# Sheet1.net
KiCad netlist of a schematic drawn in Altium Designer
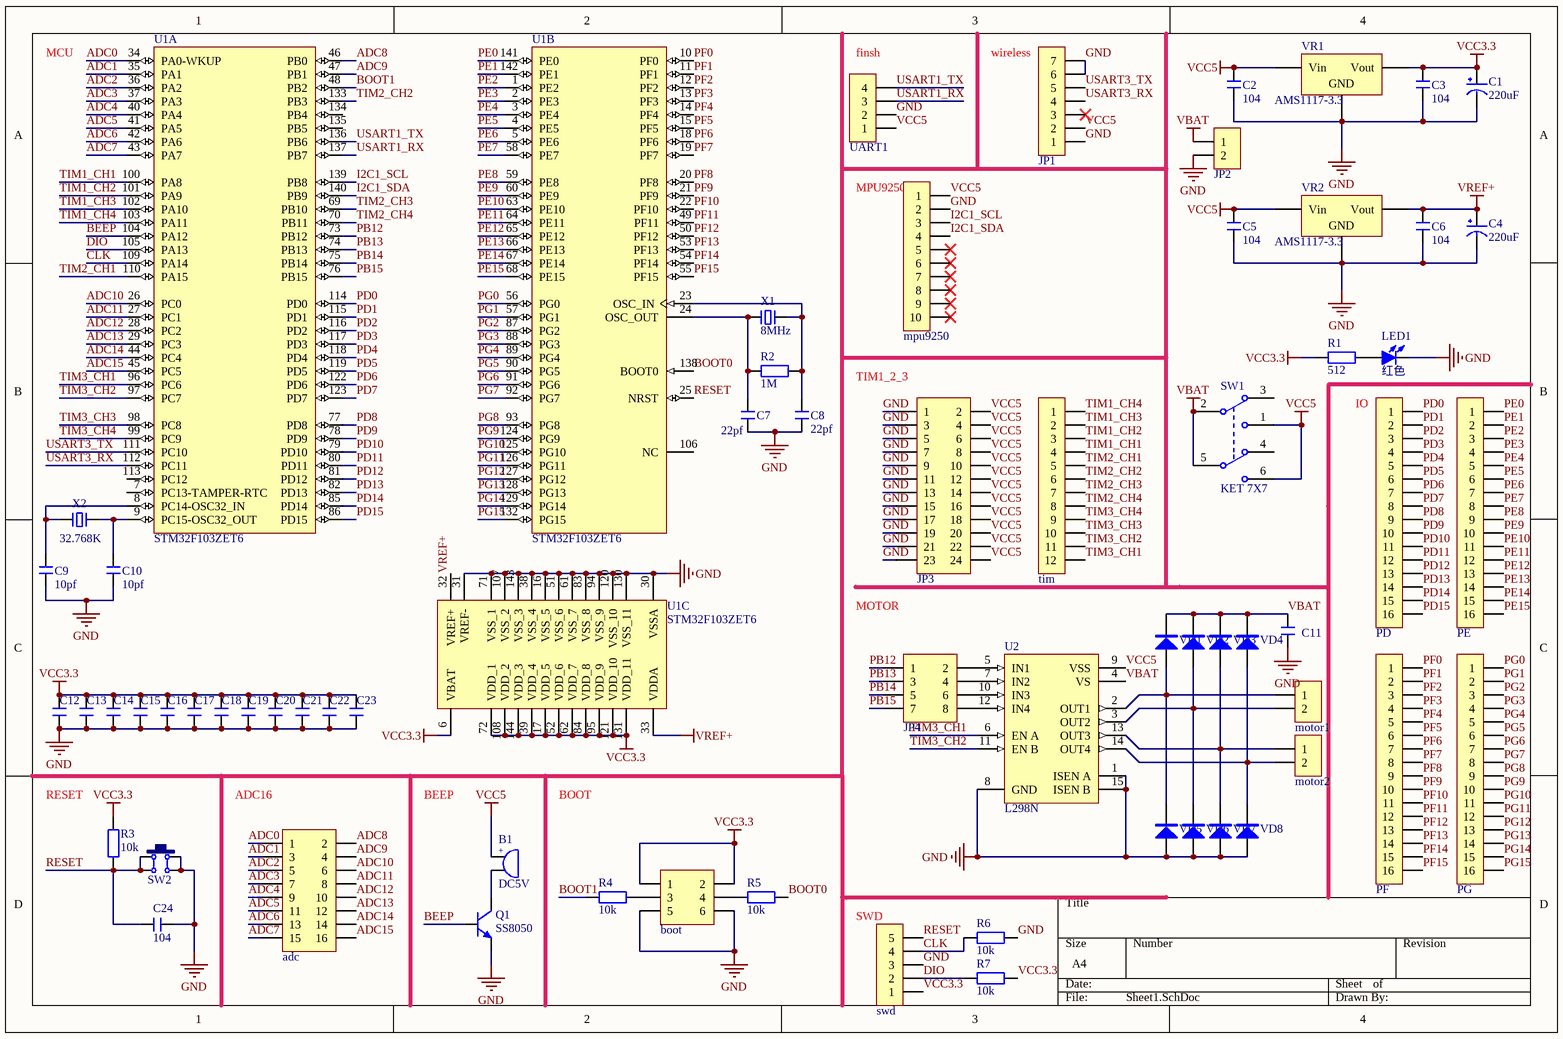
[diagram p0: Sheet1.SchDoc]

(export (version "E")
  (design (tool "Eeschema 10.0.6"))
  (components
    (comp (ref "adc")
      (value "Header 8X2")
      (footprint "HDR-8X2")
      (description "8*2P接插件")
      (fields (field (name "版权归属") "源创客"))
      (libsource (lib "接插件") (part "Header 8X2"))
    )
    (comp (ref "B1")
      (value "DC5V")
      (footprint "BEEP 5x9x5.5")
      (description "蜂鸣器")
      (fields (field (name "版权归属") "源创客"))
      (libsource (lib "未分类器件") (part "BEEP"))
    )
    (comp (ref "boot")
      (value "Header3X2")
      (footprint "HDR2X3")
      (description "3*2P接插件")
      (fields (field (name "版权归属") "源创客"))
      (libsource (lib "接插件") (part "Header 3X2"))
    )
    (comp (ref "C1")
      (value "220uF")
      (footprint "CC6.56.5")
      (libsource (lib "WarShip V3 STM32103封装库") (part "CAP"))
    )
    (comp (ref "C2")
      (value "104")
      (footprint "0805")
      (description "无极性贴片电容")
      (fields (field (name "版权归属") "源创客"))
      (libsource (lib "电阻-电容-电感") (part "C"))
    )
    (comp (ref "C3")
      (value "104")
      (footprint "0805")
      (description "无极性贴片电容")
      (fields (field (name "版权归属") "源创客"))
      (libsource (lib "电阻-电容-电感") (part "C"))
    )
    (comp (ref "C4")
      (value "220uF")
      (footprint "CC6.56.5")
      (libsource (lib "WarShip V3 STM32103封装库") (part "CAP"))
    )
    (comp (ref "C5")
      (value "104")
      (footprint "0805")
      (description "无极性贴片电容")
      (fields (field (name "版权归属") "源创客"))
      (libsource (lib "电阻-电容-电感") (part "C"))
    )
    (comp (ref "C6")
      (value "104")
      (footprint "0805")
      (description "无极性贴片电容")
      (fields (field (name "版权归属") "源创客"))
      (libsource (lib "电阻-电容-电感") (part "C"))
    )
    (comp (ref "C7")
      (value "22pf")
      (footprint "0805")
      (description "无极性贴片电容")
      (fields (field (name "版权归属") "源创客"))
      (libsource (lib "电阻-电容-电感") (part "C"))
    )
    (comp (ref "C8")
      (value "22pf")
      (footprint "0805")
      (description "无极性贴片电容")
      (fields (field (name "版权归属") "源创客"))
      (libsource (lib "电阻-电容-电感") (part "C"))
    )
    (comp (ref "C9")
      (value "10pf")
      (footprint "0805")
      (description "无极性贴片电容")
      (fields (field (name "版权归属") "源创客"))
      (libsource (lib "电阻-电容-电感") (part "C"))
    )
    (comp (ref "C10")
      (value "10pf")
      (footprint "0805")
      (description "无极性贴片电容")
      (fields (field (name "版权归属") "源创客"))
      (libsource (lib "电阻-电容-电感") (part "C"))
    )
    (comp (ref "C11")
      (value "104")
      (footprint "C 0805")
      (description "无极性贴片电容")
      (fields (field (name "版权归属") "源创客"))
      (libsource (lib "电阻-电容-电感") (part "C"))
    )
    (comp (ref "C12")
      (value "104")
      (footprint "C 0805")
      (description "无极性贴片电容")
      (fields (field (name "版权归属") "源创客"))
      (libsource (lib "电阻-电容-电感") (part "C"))
    )
    (comp (ref "C13")
      (value "104")
      (footprint "C 0805")
      (description "无极性贴片电容")
      (fields (field (name "版权归属") "源创客"))
      (libsource (lib "电阻-电容-电感") (part "C"))
    )
    (comp (ref "C14")
      (value "104")
      (footprint "C 0805")
      (description "无极性贴片电容")
      (fields (field (name "版权归属") "源创客"))
      (libsource (lib "电阻-电容-电感") (part "C"))
    )
    (comp (ref "C15")
      (value "104")
      (footprint "C 0805")
      (description "无极性贴片电容")
      (fields (field (name "版权归属") "源创客"))
      (libsource (lib "电阻-电容-电感") (part "C"))
    )
    (comp (ref "C16")
      (value "104")
      (footprint "C 0805")
      (description "无极性贴片电容")
      (fields (field (name "版权归属") "源创客"))
      (libsource (lib "电阻-电容-电感") (part "C"))
    )
    (comp (ref "C17")
      (value "104")
      (footprint "C 0805")
      (description "无极性贴片电容")
      (fields (field (name "版权归属") "源创客"))
      (libsource (lib "电阻-电容-电感") (part "C"))
    )
    (comp (ref "C18")
      (value "104")
      (footprint "C 0805")
      (description "无极性贴片电容")
      (fields (field (name "版权归属") "源创客"))
      (libsource (lib "电阻-电容-电感") (part "C"))
    )
    (comp (ref "C19")
      (value "104")
      (footprint "C 0805")
      (description "无极性贴片电容")
      (fields (field (name "版权归属") "源创客"))
      (libsource (lib "电阻-电容-电感") (part "C"))
    )
    (comp (ref "C20")
      (value "104")
      (footprint "C 0805")
      (description "无极性贴片电容")
      (fields (field (name "版权归属") "源创客"))
      (libsource (lib "电阻-电容-电感") (part "C"))
    )
    (comp (ref "C21")
      (value "104")
      (footprint "C 0805")
      (description "无极性贴片电容")
      (fields (field (name "版权归属") "源创客"))
      (libsource (lib "电阻-电容-电感") (part "C"))
    )
    (comp (ref "C22")
      (value "104")
      (footprint "C 0805")
      (description "无极性贴片电容")
      (fields (field (name "版权归属") "源创客"))
      (libsource (lib "电阻-电容-电感") (part "C"))
    )
    (comp (ref "C23")
      (value "104")
      (footprint "C 0805")
      (description "无极性贴片电容")
      (fields (field (name "版权归属") "源创客"))
      (libsource (lib "电阻-电容-电感") (part "C"))
    )
    (comp (ref "C24")
      (value "104")
      (footprint "0805")
      (description "无极性贴片电容")
      (fields (field (name "版权归属") "源创客"))
      (libsource (lib "电阻-电容-电感") (part "C"))
    )
    (comp (ref "JP1")
      (value "HDR-1X7")
      (footprint "HDR-1X7_M")
      (description "7P接插件")
      (fields (field (name "版权归属") "源创客"))
      (libsource (lib "接插件") (part "Header 7"))
    )
    (comp (ref "JP2")
      (value "HDR-1X2")
      (footprint "KF350-2P")
      (description "2P接插件")
      (fields (field (name "版权归属") "源创客"))
      (libsource (lib "接插件") (part "Header 2"))
    )
    (comp (ref "JP3")
      (value "Header 2X11")
      (footprint "HDR-12X2")
      (description "12*2P接插件")
      (fields (field (name "版权归属") "源创客"))
      (libsource (lib "接插件") (part "Header 12X2"))
    )
    (comp (ref "JP4")
      (value "Header 4X2")
      (footprint "HDR-4X2")
      (description "4*2P接插件")
      (fields (field (name "版权归属") "源创客"))
      (libsource (lib "接插件") (part "Header 4X2"))
    )
    (comp (ref "LED1")
      (value "红色")
      (footprint "LED 3MM-R")
      (description "插件LED")
      (fields (field (name "版权归属") "源创客"))
      (libsource (lib "LED") (part "LED-3MM"))
    )
    (comp (ref "motor1")
      (value "HDR-1X2")
      (footprint "KF128-3.81-2P")
      (description "2P接插件")
      (fields (field (name "版权归属") "源创客"))
      (libsource (lib "接插件") (part "Header 2"))
    )
    (comp (ref "motor2")
      (value "HDR-1X2")
      (footprint "KF128-3.81-2P")
      (description "2P接插件")
      (fields (field (name "版权归属") "源创客"))
      (libsource (lib "接插件") (part "Header 2"))
    )
    (comp (ref "mpu9250")
      (value "HDR-1X10")
      (footprint "HDR-1X10_M")
      (description "10P接插件")
      (fields (field (name "版权归属") "源创客"))
      (libsource (lib "接插件") (part "Header 10"))
    )
    (comp (ref "PD")
      (value "HDR-1X16")
      (footprint "HDR-1X16")
      (description "16P接插件")
      (fields (field (name "版权归属") "源创客"))
      (libsource (lib "接插件") (part "Header 16"))
    )
    (comp (ref "PE")
      (value "HDR-1X16")
      (footprint "HDR-1X16")
      (description "16P接插件")
      (fields (field (name "版权归属") "源创客"))
      (libsource (lib "接插件") (part "Header 16"))
    )
    (comp (ref "PF")
      (value "HDR-1X16")
      (footprint "HDR-1X16")
      (description "16P接插件")
      (fields (field (name "版权归属") "源创客"))
      (libsource (lib "接插件") (part "Header 16"))
    )
    (comp (ref "PG")
      (value "HDR-1X16")
      (footprint "HDR-1X16")
      (description "16P接插件")
      (fields (field (name "版权归属") "源创客"))
      (libsource (lib "接插件") (part "Header 16"))
    )
    (comp (ref "Q1")
      (value "SS8050")
      (footprint "TO92A")
      (description "高频放大-NPN型")
      (fields (field (name "版权归属") "源创客"))
      (libsource (lib "三极管") (part "8050-DIP"))
    )
    (comp (ref "R1")
      (value "512")
      (footprint "0805")
      (description "贴片电阻")
      (fields (field (name "版权归属") "源创客"))
      (libsource (lib "电阻-电容-电感") (part "R"))
    )
    (comp (ref "R2")
      (value "1M")
      (footprint "0805")
      (description "贴片电阻")
      (fields (field (name "版权归属") "源创客"))
      (libsource (lib "电阻-电容-电感") (part "R"))
    )
    (comp (ref "R3")
      (value "10k")
      (footprint "0805")
      (description "贴片电阻")
      (fields (field (name "版权归属") "源创客"))
      (libsource (lib "电阻-电容-电感") (part "R"))
    )
    (comp (ref "R4")
      (value "10k")
      (footprint "0805")
      (description "贴片电阻")
      (fields (field (name "版权归属") "源创客"))
      (libsource (lib "电阻-电容-电感") (part "R"))
    )
    (comp (ref "R5")
      (value "10k")
      (footprint "0805")
      (description "贴片电阻")
      (fields (field (name "版权归属") "源创客"))
      (libsource (lib "电阻-电容-电感") (part "R"))
    )
    (comp (ref "R6")
      (value "10k")
      (footprint "R 0805")
      (description "贴片电阻")
      (fields (field (name "版权归属") "源创客"))
      (libsource (lib "电阻-电容-电感") (part "R"))
    )
    (comp (ref "R7")
      (value "10k")
      (footprint "R 0805")
      (description "贴片电阻")
      (fields (field (name "版权归属") "源创客"))
      (libsource (lib "电阻-电容-电感") (part "R"))
    )
    (comp (ref "SW1")
      (value "KET 7X7")
      (footprint "KFT DIP-7X7")
      (description "7*7自锁开关")
      (fields (field (name "版权归属") "源创客"))
      (libsource (lib "按键-开关") (part "KET 7X7"))
    )
    (comp (ref "SW2")
      (value "6x6x5")
      (footprint "TSW DIP-6*6*5")
      (description "直插6x6轻触开关")
      (fields (field (name "版权归属") "源创客"))
      (libsource (lib "按键-开关") (part "TSW DIP-6x6"))
    )
    (comp (ref "swd")
      (value "HDR-1X5")
      (footprint "HDR-1X5")
      (description "5P接插件")
      (fields (field (name "版权归属") "源创客"))
      (libsource (lib "接插件") (part "Header 5"))
    )
    (comp (ref "tim")
      (value "HDR-1X12")
      (footprint "HDR-1X12_M")
      (description "12P接插件")
      (fields (field (name "版权归属") "源创客"))
      (libsource (lib "接插件") (part "Header 12"))
    )
    (comp (ref "U1")
      (value "STM32F103ZET6")
      (footprint "STM-LQFP144_M")
      (libsource (lib "") (part "STM32F103ZET6_1"))
    )
    (comp (ref "U2")
      (value "L298N")
      (footprint "Multiwatt15V")
      (description "Dual Full Bridge Driver")
      (fields (field (name "PUBLISHER") "Altium Limited"))
      (libsource (lib "ST Interface DC Motor Controller") (part "L298N"))
    )
    (comp (ref "UART1")
      (value "HDR-1X4")
      (footprint "HDR1X4")
      (description "4P接插件")
      (fields (field (name "版权归属") "源创客"))
      (libsource (lib "接插件") (part "Header 4"))
    )
    (comp (ref "VD1")
      (value "1N4007")
      (footprint "SMA")
      (description "整流二极管")
      (fields (field (name "版权归属") "源创客"))
      (libsource (lib "二极管-整流桥") (part "1N4007"))
    )
    (comp (ref "VD2")
      (value "1N4007")
      (footprint "SMA")
      (description "整流二极管")
      (fields (field (name "版权归属") "源创客"))
      (libsource (lib "二极管-整流桥") (part "1N4007"))
    )
    (comp (ref "VD3")
      (value "1N4007")
      (footprint "SMA")
      (description "整流二极管")
      (fields (field (name "版权归属") "源创客"))
      (libsource (lib "二极管-整流桥") (part "1N4007"))
    )
    (comp (ref "VD4")
      (value "1N4007")
      (footprint "SMA")
      (description "整流二极管")
      (fields (field (name "版权归属") "源创客"))
      (libsource (lib "二极管-整流桥") (part "1N4007"))
    )
    (comp (ref "VD5")
      (value "1N4007")
      (footprint "SMA")
      (description "整流二极管")
      (fields (field (name "版权归属") "源创客"))
      (libsource (lib "二极管-整流桥") (part "1N4007"))
    )
    (comp (ref "VD6")
      (value "1N4007")
      (footprint "SMA")
      (description "整流二极管")
      (fields (field (name "版权归属") "源创客"))
      (libsource (lib "二极管-整流桥") (part "1N4007"))
    )
    (comp (ref "VD7")
      (value "1N4007")
      (footprint "SMA")
      (description "整流二极管")
      (fields (field (name "版权归属") "源创客"))
      (libsource (lib "二极管-整流桥") (part "1N4007"))
    )
    (comp (ref "VD8")
      (value "1N4007")
      (footprint "SMA")
      (description "整流二极管")
      (fields (field (name "版权归属") "源创客"))
      (libsource (lib "二极管-整流桥") (part "1N4007"))
    )
    (comp (ref "VR1")
      (value "AMS1117-3.3")
      (footprint "SOT-223")
      (description "低压差线性稳压(LDO)")
      (libsource (lib "Miscellaneous Devices LC") (part "SOT-223 AMS1117-3.3"))
    )
    (comp (ref "VR2")
      (value "AMS1117-3.3")
      (footprint "SOT-223")
      (description "低压差线性稳压(LDO)")
      (libsource (lib "Miscellaneous Devices LC") (part "SOT-223 AMS1117-3.3"))
    )
    (comp (ref "X1")
      (value "8MHz")
      (footprint "XTAL-49S DIP")
      (description "2脚晶振")
      (fields (field (name "版权归属") "源创客"))
      (libsource (lib "保险丝-晶振") (part "XTAL-2"))
    )
    (comp (ref "X2")
      (value "32.768K")
      (footprint "CAPR5-4X5")
      (description "2脚晶振")
      (fields (field (name "版权归属") "源创客"))
      (libsource (lib "保险丝-晶振") (part "XTAL-2"))
    )
  )
  (nets
    (net (code "1") (name "/ADC0") (class "Default")
      (node (ref "U1") (pin "34") (pinfunction "PA0-WKUP_34") (pintype "bidirectional"))
      (node (ref "adc") (pin "1") (pinfunction "1_1") (pintype "passive"))
    )
    (net (code "2") (name "/ADC1") (class "Default")
      (node (ref "U1") (pin "35") (pinfunction "PA1_35") (pintype "bidirectional"))
      (node (ref "adc") (pin "3") (pinfunction "3_3") (pintype "passive"))
    )
    (net (code "3") (name "/ADC2") (class "Default")
      (node (ref "U1") (pin "36") (pinfunction "PA2_36") (pintype "bidirectional"))
      (node (ref "adc") (pin "5") (pinfunction "5_5") (pintype "passive"))
    )
    (net (code "4") (name "/ADC3") (class "Default")
      (node (ref "U1") (pin "37") (pinfunction "PA3_37") (pintype "bidirectional"))
      (node (ref "adc") (pin "7") (pinfunction "7_7") (pintype "passive"))
    )
    (net (code "5") (name "/ADC4") (class "Default")
      (node (ref "U1") (pin "40") (pinfunction "PA4_40") (pintype "bidirectional"))
      (node (ref "adc") (pin "9") (pinfunction "9_9") (pintype "passive"))
    )
    (net (code "6") (name "/ADC5") (class "Default")
      (node (ref "U1") (pin "41") (pinfunction "PA5_41") (pintype "bidirectional"))
      (node (ref "adc") (pin "11") (pinfunction "11_11") (pintype "passive"))
    )
    (net (code "7") (name "/ADC6") (class "Default")
      (node (ref "U1") (pin "42") (pinfunction "PA6_42") (pintype "bidirectional"))
      (node (ref "adc") (pin "13") (pinfunction "13_13") (pintype "passive"))
    )
    (net (code "8") (name "/ADC7") (class "Default")
      (node (ref "U1") (pin "43") (pinfunction "PA7_43") (pintype "bidirectional"))
      (node (ref "adc") (pin "15") (pinfunction "15_15") (pintype "passive"))
    )
    (net (code "9") (name "/ADC8") (class "Default")
      (node (ref "U1") (pin "46") (pinfunction "PB0_46") (pintype "bidirectional"))
      (node (ref "adc") (pin "2") (pinfunction "2_2") (pintype "passive"))
    )
    (net (code "10") (name "/ADC9") (class "Default")
      (node (ref "U1") (pin "47") (pinfunction "PB1_47") (pintype "bidirectional"))
      (node (ref "adc") (pin "4") (pinfunction "4_4") (pintype "passive"))
    )
    (net (code "11") (name "/ADC10") (class "Default")
      (node (ref "U1") (pin "26") (pinfunction "PC0_26") (pintype "bidirectional"))
      (node (ref "adc") (pin "6") (pinfunction "6_6") (pintype "passive"))
    )
    (net (code "12") (name "/ADC11") (class "Default")
      (node (ref "U1") (pin "27") (pinfunction "PC1_27") (pintype "bidirectional"))
      (node (ref "adc") (pin "8") (pinfunction "8_8") (pintype "passive"))
    )
    (net (code "13") (name "/ADC12") (class "Default")
      (node (ref "U1") (pin "28") (pinfunction "PC2_28") (pintype "bidirectional"))
      (node (ref "adc") (pin "10") (pinfunction "10_10") (pintype "passive"))
    )
    (net (code "14") (name "/ADC13") (class "Default")
      (node (ref "U1") (pin "29") (pinfunction "PC3_29") (pintype "bidirectional"))
      (node (ref "adc") (pin "12") (pinfunction "12_12") (pintype "passive"))
    )
    (net (code "15") (name "/ADC14") (class "Default")
      (node (ref "U1") (pin "44") (pinfunction "PC4_44") (pintype "bidirectional"))
      (node (ref "adc") (pin "14") (pinfunction "14_14") (pintype "passive"))
    )
    (net (code "16") (name "/ADC15") (class "Default")
      (node (ref "U1") (pin "45") (pinfunction "PC5_45") (pintype "bidirectional"))
      (node (ref "adc") (pin "16") (pinfunction "16_16") (pintype "passive"))
    )
    (net (code "17") (name "/BEEP") (class "Default")
      (node (ref "Q1") (pin "2") (pinfunction "B_2") (pintype "passive"))
      (node (ref "U1") (pin "104") (pinfunction "PA12_104") (pintype "bidirectional"))
    )
    (net (code "18") (name "/BOOT0") (class "Default")
      (node (ref "R5") (pin "1") (pinfunction "1_1") (pintype "passive"))
      (node (ref "U1") (pin "138") (pinfunction "BOOT0_138") (pintype "input"))
    )
    (net (code "19") (name "/BOOT1") (class "Default")
      (node (ref "R4") (pin "1") (pinfunction "1_1") (pintype "passive"))
      (node (ref "U1") (pin "48") (pinfunction "PB2_48") (pintype "bidirectional"))
    )
    (net (code "20") (name "/CLK") (class "Default")
      (node (ref "R6") (pin "1") (pinfunction "1_1") (pintype "passive"))
      (node (ref "U1") (pin "109") (pinfunction "PA14_109") (pintype "bidirectional"))
      (node (ref "swd") (pin "4") (pinfunction "4_4") (pintype "passive"))
    )
    (net (code "21") (name "/DIO") (class "Default")
      (node (ref "R7") (pin "1") (pinfunction "1_1") (pintype "passive"))
      (node (ref "U1") (pin "105") (pinfunction "PA13_105") (pintype "bidirectional"))
      (node (ref "swd") (pin "2") (pinfunction "2_2") (pintype "passive"))
    )
    (net (code "22") (name "/I2C1_SCL") (class "Default")
      (node (ref "U1") (pin "139") (pinfunction "PB8_139") (pintype "bidirectional"))
      (node (ref "mpu9250") (pin "3") (pinfunction "3_3") (pintype "passive"))
    )
    (net (code "23") (name "/I2C1_SDA") (class "Default")
      (node (ref "U1") (pin "140") (pinfunction "PB9_140") (pintype "bidirectional"))
      (node (ref "mpu9250") (pin "4") (pinfunction "4_4") (pintype "passive"))
    )
    (net (code "24") (name "/PB12") (class "Default")
      (node (ref "JP4") (pin "1") (pinfunction "1_1") (pintype "passive"))
      (node (ref "U1") (pin "73") (pinfunction "PB12_73") (pintype "bidirectional"))
    )
    (net (code "25") (name "/PB13") (class "Default")
      (node (ref "JP4") (pin "3") (pinfunction "3_3") (pintype "passive"))
      (node (ref "U1") (pin "74") (pinfunction "PB13_74") (pintype "bidirectional"))
    )
    (net (code "26") (name "/PB14") (class "Default")
      (node (ref "JP4") (pin "5") (pinfunction "5_5") (pintype "passive"))
      (node (ref "U1") (pin "75") (pinfunction "PB14_75") (pintype "bidirectional"))
    )
    (net (code "27") (name "/PB15") (class "Default")
      (node (ref "JP4") (pin "7") (pinfunction "7_7") (pintype "passive"))
      (node (ref "U1") (pin "76") (pinfunction "PB15_76") (pintype "bidirectional"))
    )
    (net (code "28") (name "/PD0") (class "Default")
      (node (ref "PD") (pin "1") (pinfunction "1_1") (pintype "passive"))
      (node (ref "U1") (pin "114") (pinfunction "PD0_114") (pintype "bidirectional"))
    )
    (net (code "29") (name "/PD1") (class "Default")
      (node (ref "PD") (pin "2") (pinfunction "2_2") (pintype "passive"))
      (node (ref "U1") (pin "115") (pinfunction "PD1_115") (pintype "bidirectional"))
    )
    (net (code "30") (name "/PD2") (class "Default")
      (node (ref "PD") (pin "3") (pinfunction "3_3") (pintype "passive"))
      (node (ref "U1") (pin "116") (pinfunction "PD2_116") (pintype "bidirectional"))
    )
    (net (code "31") (name "/PD3") (class "Default")
      (node (ref "PD") (pin "4") (pinfunction "4_4") (pintype "passive"))
      (node (ref "U1") (pin "117") (pinfunction "PD3_117") (pintype "bidirectional"))
    )
    (net (code "32") (name "/PD4") (class "Default")
      (node (ref "PD") (pin "5") (pinfunction "5_5") (pintype "passive"))
      (node (ref "U1") (pin "118") (pinfunction "PD4_118") (pintype "bidirectional"))
    )
    (net (code "33") (name "/PD5") (class "Default")
      (node (ref "PD") (pin "6") (pinfunction "6_6") (pintype "passive"))
      (node (ref "U1") (pin "119") (pinfunction "PD5_119") (pintype "bidirectional"))
    )
    (net (code "34") (name "/PD6") (class "Default")
      (node (ref "PD") (pin "7") (pinfunction "7_7") (pintype "passive"))
      (node (ref "U1") (pin "122") (pinfunction "PD6_122") (pintype "bidirectional"))
    )
    (net (code "35") (name "/PD7") (class "Default")
      (node (ref "PD") (pin "8") (pinfunction "8_8") (pintype "passive"))
      (node (ref "U1") (pin "123") (pinfunction "PD7_123") (pintype "bidirectional"))
    )
    (net (code "36") (name "/PD8") (class "Default")
      (node (ref "PD") (pin "9") (pinfunction "9_9") (pintype "passive"))
      (node (ref "U1") (pin "77") (pinfunction "PD8_77") (pintype "bidirectional"))
    )
    (net (code "37") (name "/PD9") (class "Default")
      (node (ref "PD") (pin "10") (pinfunction "10_10") (pintype "passive"))
      (node (ref "U1") (pin "78") (pinfunction "PD9_78") (pintype "bidirectional"))
    )
    (net (code "38") (name "/PD10") (class "Default")
      (node (ref "PD") (pin "11") (pinfunction "11_11") (pintype "passive"))
      (node (ref "U1") (pin "79") (pinfunction "PD10_79") (pintype "bidirectional"))
    )
    (net (code "39") (name "/PD11") (class "Default")
      (node (ref "PD") (pin "12") (pinfunction "12_12") (pintype "passive"))
      (node (ref "U1") (pin "80") (pinfunction "PD11_80") (pintype "bidirectional"))
    )
    (net (code "40") (name "/PD12") (class "Default")
      (node (ref "PD") (pin "13") (pinfunction "13_13") (pintype "passive"))
      (node (ref "U1") (pin "81") (pinfunction "PD12_81") (pintype "bidirectional"))
    )
    (net (code "41") (name "/PD13") (class "Default")
      (node (ref "PD") (pin "14") (pinfunction "14_14") (pintype "passive"))
      (node (ref "U1") (pin "82") (pinfunction "PD13_82") (pintype "bidirectional"))
    )
    (net (code "42") (name "/PD14") (class "Default")
      (node (ref "PD") (pin "15") (pinfunction "15_15") (pintype "passive"))
      (node (ref "U1") (pin "85") (pinfunction "PD14_85") (pintype "bidirectional"))
    )
    (net (code "43") (name "/PD15") (class "Default")
      (node (ref "PD") (pin "16") (pinfunction "16_16") (pintype "passive"))
      (node (ref "U1") (pin "86") (pinfunction "PD15_86") (pintype "bidirectional"))
    )
    (net (code "44") (name "/PE0") (class "Default")
      (node (ref "PE") (pin "1") (pinfunction "1_1") (pintype "passive"))
      (node (ref "U1") (pin "141") (pinfunction "PE0_141") (pintype "bidirectional"))
    )
    (net (code "45") (name "/PE1") (class "Default")
      (node (ref "PE") (pin "2") (pinfunction "2_2") (pintype "passive"))
      (node (ref "U1") (pin "142") (pinfunction "PE1_142") (pintype "bidirectional"))
    )
    (net (code "46") (name "/PE2") (class "Default")
      (node (ref "PE") (pin "3") (pinfunction "3_3") (pintype "passive"))
      (node (ref "U1") (pin "1") (pinfunction "PE2_1") (pintype "bidirectional"))
    )
    (net (code "47") (name "/PE3") (class "Default")
      (node (ref "PE") (pin "4") (pinfunction "4_4") (pintype "passive"))
      (node (ref "U1") (pin "2") (pinfunction "PE3_2") (pintype "bidirectional"))
    )
    (net (code "48") (name "/PE4") (class "Default")
      (node (ref "PE") (pin "5") (pinfunction "5_5") (pintype "passive"))
      (node (ref "U1") (pin "3") (pinfunction "PE4_3") (pintype "bidirectional"))
    )
    (net (code "49") (name "/PE5") (class "Default")
      (node (ref "PE") (pin "6") (pinfunction "6_6") (pintype "passive"))
      (node (ref "U1") (pin "4") (pinfunction "PE5_4") (pintype "bidirectional"))
    )
    (net (code "50") (name "/PE6") (class "Default")
      (node (ref "PE") (pin "7") (pinfunction "7_7") (pintype "passive"))
      (node (ref "U1") (pin "5") (pinfunction "PE6_5") (pintype "bidirectional"))
    )
    (net (code "51") (name "/PE7") (class "Default")
      (node (ref "PE") (pin "8") (pinfunction "8_8") (pintype "passive"))
      (node (ref "U1") (pin "58") (pinfunction "PE7_58") (pintype "bidirectional"))
    )
    (net (code "52") (name "/PE8") (class "Default")
      (node (ref "PE") (pin "9") (pinfunction "9_9") (pintype "passive"))
      (node (ref "U1") (pin "59") (pinfunction "PE8_59") (pintype "bidirectional"))
    )
    (net (code "53") (name "/PE9") (class "Default")
      (node (ref "PE") (pin "10") (pinfunction "10_10") (pintype "passive"))
      (node (ref "U1") (pin "60") (pinfunction "PE9_60") (pintype "bidirectional"))
    )
    (net (code "54") (name "/PE10") (class "Default")
      (node (ref "PE") (pin "11") (pinfunction "11_11") (pintype "passive"))
      (node (ref "U1") (pin "63") (pinfunction "PE10_63") (pintype "bidirectional"))
    )
    (net (code "55") (name "/PE11") (class "Default")
      (node (ref "PE") (pin "12") (pinfunction "12_12") (pintype "passive"))
      (node (ref "U1") (pin "64") (pinfunction "PE11_64") (pintype "bidirectional"))
    )
    (net (code "56") (name "/PE12") (class "Default")
      (node (ref "PE") (pin "13") (pinfunction "13_13") (pintype "passive"))
      (node (ref "U1") (pin "65") (pinfunction "PE12_65") (pintype "bidirectional"))
    )
    (net (code "57") (name "/PE13") (class "Default")
      (node (ref "PE") (pin "14") (pinfunction "14_14") (pintype "passive"))
      (node (ref "U1") (pin "66") (pinfunction "PE13_66") (pintype "bidirectional"))
    )
    (net (code "58") (name "/PE14") (class "Default")
      (node (ref "PE") (pin "15") (pinfunction "15_15") (pintype "passive"))
      (node (ref "U1") (pin "67") (pinfunction "PE14_67") (pintype "bidirectional"))
    )
    (net (code "59") (name "/PE15") (class "Default")
      (node (ref "PE") (pin "16") (pinfunction "16_16") (pintype "passive"))
      (node (ref "U1") (pin "68") (pinfunction "PE15_68") (pintype "bidirectional"))
    )
    (net (code "60") (name "/PF0") (class "Default")
      (node (ref "PF") (pin "1") (pinfunction "1_1") (pintype "passive"))
      (node (ref "U1") (pin "10") (pinfunction "PF0_10") (pintype "bidirectional"))
    )
    (net (code "61") (name "/PF1") (class "Default")
      (node (ref "PF") (pin "2") (pinfunction "2_2") (pintype "passive"))
      (node (ref "U1") (pin "11") (pinfunction "PF1_11") (pintype "bidirectional"))
    )
    (net (code "62") (name "/PF2") (class "Default")
      (node (ref "PF") (pin "3") (pinfunction "3_3") (pintype "passive"))
      (node (ref "U1") (pin "12") (pinfunction "PF2_12") (pintype "bidirectional"))
    )
    (net (code "63") (name "/PF3") (class "Default")
      (node (ref "PF") (pin "4") (pinfunction "4_4") (pintype "passive"))
      (node (ref "U1") (pin "13") (pinfunction "PF3_13") (pintype "bidirectional"))
    )
    (net (code "64") (name "/PF4") (class "Default")
      (node (ref "PF") (pin "5") (pinfunction "5_5") (pintype "passive"))
      (node (ref "U1") (pin "14") (pinfunction "PF4_14") (pintype "bidirectional"))
    )
    (net (code "65") (name "/PF5") (class "Default")
      (node (ref "PF") (pin "6") (pinfunction "6_6") (pintype "passive"))
      (node (ref "U1") (pin "15") (pinfunction "PF5_15") (pintype "bidirectional"))
    )
    (net (code "66") (name "/PF6") (class "Default")
      (node (ref "PF") (pin "7") (pinfunction "7_7") (pintype "passive"))
      (node (ref "U1") (pin "18") (pinfunction "PF6_18") (pintype "bidirectional"))
    )
    (net (code "67") (name "/PF7") (class "Default")
      (node (ref "PF") (pin "8") (pinfunction "8_8") (pintype "passive"))
      (node (ref "U1") (pin "19") (pinfunction "PF7_19") (pintype "bidirectional"))
    )
    (net (code "68") (name "/PF8") (class "Default")
      (node (ref "PF") (pin "9") (pinfunction "9_9") (pintype "passive"))
      (node (ref "U1") (pin "20") (pinfunction "PF8_20") (pintype "bidirectional"))
    )
    (net (code "69") (name "/PF9") (class "Default")
      (node (ref "PF") (pin "10") (pinfunction "10_10") (pintype "passive"))
      (node (ref "U1") (pin "21") (pinfunction "PF9_21") (pintype "bidirectional"))
    )
    (net (code "70") (name "/PF10") (class "Default")
      (node (ref "PF") (pin "11") (pinfunction "11_11") (pintype "passive"))
      (node (ref "U1") (pin "22") (pinfunction "PF10_22") (pintype "bidirectional"))
    )
    (net (code "71") (name "/PF11") (class "Default")
      (node (ref "PF") (pin "12") (pinfunction "12_12") (pintype "passive"))
      (node (ref "U1") (pin "49") (pinfunction "PF11_49") (pintype "bidirectional"))
    )
    (net (code "72") (name "/PF12") (class "Default")
      (node (ref "PF") (pin "13") (pinfunction "13_13") (pintype "passive"))
      (node (ref "U1") (pin "50") (pinfunction "PF12_50") (pintype "bidirectional"))
    )
    (net (code "73") (name "/PF13") (class "Default")
      (node (ref "PF") (pin "14") (pinfunction "14_14") (pintype "passive"))
      (node (ref "U1") (pin "53") (pinfunction "PF13_53") (pintype "bidirectional"))
    )
    (net (code "74") (name "/PF14") (class "Default")
      (node (ref "PF") (pin "15") (pinfunction "15_15") (pintype "passive"))
      (node (ref "U1") (pin "54") (pinfunction "PF14_54") (pintype "bidirectional"))
    )
    (net (code "75") (name "/PF15") (class "Default")
      (node (ref "PF") (pin "16") (pinfunction "16_16") (pintype "passive"))
      (node (ref "U1") (pin "55") (pinfunction "PF15_55") (pintype "bidirectional"))
    )
    (net (code "76") (name "/PG0") (class "Default")
      (node (ref "PG") (pin "1") (pinfunction "1_1") (pintype "passive"))
      (node (ref "U1") (pin "56") (pinfunction "PG0_56") (pintype "bidirectional"))
    )
    (net (code "77") (name "/PG1") (class "Default")
      (node (ref "PG") (pin "2") (pinfunction "2_2") (pintype "passive"))
      (node (ref "U1") (pin "57") (pinfunction "PG1_57") (pintype "bidirectional"))
    )
    (net (code "78") (name "/PG2") (class "Default")
      (node (ref "PG") (pin "3") (pinfunction "3_3") (pintype "passive"))
      (node (ref "U1") (pin "87") (pinfunction "PG2_87") (pintype "bidirectional"))
    )
    (net (code "79") (name "/PG3") (class "Default")
      (node (ref "PG") (pin "4") (pinfunction "4_4") (pintype "passive"))
      (node (ref "U1") (pin "88") (pinfunction "PG3_88") (pintype "bidirectional"))
    )
    (net (code "80") (name "/PG4") (class "Default")
      (node (ref "PG") (pin "5") (pinfunction "5_5") (pintype "passive"))
      (node (ref "U1") (pin "89") (pinfunction "PG4_89") (pintype "bidirectional"))
    )
    (net (code "81") (name "/PG5") (class "Default")
      (node (ref "PG") (pin "6") (pinfunction "6_6") (pintype "passive"))
      (node (ref "U1") (pin "90") (pinfunction "PG5_90") (pintype "bidirectional"))
    )
    (net (code "82") (name "/PG6") (class "Default")
      (node (ref "PG") (pin "7") (pinfunction "7_7") (pintype "passive"))
      (node (ref "U1") (pin "91") (pinfunction "PG6_91") (pintype "bidirectional"))
    )
    (net (code "83") (name "/PG7") (class "Default")
      (node (ref "PG") (pin "8") (pinfunction "8_8") (pintype "passive"))
      (node (ref "U1") (pin "92") (pinfunction "PG7_92") (pintype "bidirectional"))
    )
    (net (code "84") (name "/PG8") (class "Default")
      (node (ref "PG") (pin "9") (pinfunction "9_9") (pintype "passive"))
      (node (ref "U1") (pin "93") (pinfunction "PG8_93") (pintype "bidirectional"))
    )
    (net (code "85") (name "/PG9") (class "Default")
      (node (ref "PG") (pin "10") (pinfunction "10_10") (pintype "passive"))
      (node (ref "U1") (pin "124") (pinfunction "PG9_124") (pintype "bidirectional"))
    )
    (net (code "86") (name "/PG10") (class "Default")
      (node (ref "PG") (pin "11") (pinfunction "11_11") (pintype "passive"))
      (node (ref "U1") (pin "125") (pinfunction "PG10_125") (pintype "bidirectional"))
    )
    (net (code "87") (name "/PG11") (class "Default")
      (node (ref "PG") (pin "12") (pinfunction "12_12") (pintype "passive"))
      (node (ref "U1") (pin "126") (pinfunction "PG11_126") (pintype "bidirectional"))
    )
    (net (code "88") (name "/PG12") (class "Default")
      (node (ref "PG") (pin "13") (pinfunction "13_13") (pintype "passive"))
      (node (ref "U1") (pin "127") (pinfunction "PG12_127") (pintype "bidirectional"))
    )
    (net (code "89") (name "/PG13") (class "Default")
      (node (ref "PG") (pin "14") (pinfunction "14_14") (pintype "passive"))
      (node (ref "U1") (pin "128") (pinfunction "PG13_128") (pintype "bidirectional"))
    )
    (net (code "90") (name "/PG14") (class "Default")
      (node (ref "PG") (pin "15") (pinfunction "15_15") (pintype "passive"))
      (node (ref "U1") (pin "129") (pinfunction "PG14_129") (pintype "bidirectional"))
    )
    (net (code "91") (name "/PG15") (class "Default")
      (node (ref "PG") (pin "16") (pinfunction "16_16") (pintype "passive"))
      (node (ref "U1") (pin "132") (pinfunction "PG15_132") (pintype "bidirectional"))
    )
    (net (code "92") (name "/RESET") (class "Default")
      (node (ref "C24") (pin "1") (pinfunction "1_1") (pintype "passive"))
      (node (ref "R3") (pin "1") (pinfunction "1_1") (pintype "passive"))
      (node (ref "SW2") (pin "1") (pinfunction "1_1") (pintype "passive"))
      (node (ref "SW2") (pin "4") (pinfunction "4_4") (pintype "passive"))
      (node (ref "U1") (pin "25") (pinfunction "NRST_25") (pintype "bidirectional"))
      (node (ref "swd") (pin "5") (pinfunction "5_5") (pintype "passive"))
    )
    (net (code "93") (name "/TIM1_CH1") (class "Default")
      (node (ref "U1") (pin "100") (pinfunction "PA8_100") (pintype "bidirectional"))
      (node (ref "tim") (pin "4") (pinfunction "4_4") (pintype "passive"))
    )
    (net (code "94") (name "/TIM1_CH2") (class "Default")
      (node (ref "U1") (pin "101") (pinfunction "PA9_101") (pintype "bidirectional"))
      (node (ref "tim") (pin "3") (pinfunction "3_3") (pintype "passive"))
    )
    (net (code "95") (name "/TIM1_CH3") (class "Default")
      (node (ref "U1") (pin "102") (pinfunction "PA10_102") (pintype "bidirectional"))
      (node (ref "tim") (pin "2") (pinfunction "2_2") (pintype "passive"))
    )
    (net (code "96") (name "/TIM1_CH4") (class "Default")
      (node (ref "U1") (pin "103") (pinfunction "PA11_103") (pintype "bidirectional"))
      (node (ref "tim") (pin "1") (pinfunction "1_1") (pintype "passive"))
    )
    (net (code "97") (name "/TIM2_CH1") (class "Default")
      (node (ref "U1") (pin "110") (pinfunction "PA15_110") (pintype "bidirectional"))
      (node (ref "tim") (pin "5") (pinfunction "5_5") (pintype "passive"))
    )
    (net (code "98") (name "/TIM2_CH2") (class "Default")
      (node (ref "U1") (pin "133") (pinfunction "PB3_133") (pintype "bidirectional"))
      (node (ref "tim") (pin "6") (pinfunction "6_6") (pintype "passive"))
    )
    (net (code "99") (name "/TIM2_CH3") (class "Default")
      (node (ref "U1") (pin "69") (pinfunction "PB10_69") (pintype "bidirectional"))
      (node (ref "tim") (pin "7") (pinfunction "7_7") (pintype "passive"))
    )
    (net (code "100") (name "/TIM2_CH4") (class "Default")
      (node (ref "U1") (pin "70") (pinfunction "PB11_70") (pintype "bidirectional"))
      (node (ref "tim") (pin "8") (pinfunction "8_8") (pintype "passive"))
    )
    (net (code "101") (name "/TIM3_CH1") (class "Default")
      (node (ref "U1") (pin "96") (pinfunction "PC6_96") (pintype "bidirectional"))
      (node (ref "U2") (pin "6") (pinfunction "EN_A_6") (pintype "input"))
      (node (ref "tim") (pin "12") (pinfunction "12_12") (pintype "passive"))
    )
    (net (code "102") (name "/TIM3_CH2") (class "Default")
      (node (ref "U1") (pin "97") (pinfunction "PC7_97") (pintype "bidirectional"))
      (node (ref "U2") (pin "11") (pinfunction "EN_B_11") (pintype "input"))
      (node (ref "tim") (pin "11") (pinfunction "11_11") (pintype "passive"))
    )
    (net (code "103") (name "/TIM3_CH3") (class "Default")
      (node (ref "U1") (pin "98") (pinfunction "PC8_98") (pintype "bidirectional"))
      (node (ref "tim") (pin "10") (pinfunction "10_10") (pintype "passive"))
    )
    (net (code "104") (name "/TIM3_CH4") (class "Default")
      (node (ref "U1") (pin "99") (pinfunction "PC9_99") (pintype "bidirectional"))
      (node (ref "tim") (pin "9") (pinfunction "9_9") (pintype "passive"))
    )
    (net (code "105") (name "/USART1_RX") (class "Default")
      (node (ref "U1") (pin "137") (pinfunction "PB7_137") (pintype "bidirectional"))
      (node (ref "UART1") (pin "3") (pinfunction "3_3") (pintype "passive"))
    )
    (net (code "106") (name "/USART1_TX") (class "Default")
      (node (ref "U1") (pin "136") (pinfunction "PB6_136") (pintype "bidirectional"))
      (node (ref "UART1") (pin "4") (pinfunction "4_4") (pintype "passive"))
    )
    (net (code "107") (name "/USART3_RX") (class "Default")
      (node (ref "JP1") (pin "4") (pinfunction "4_4") (pintype "passive"))
      (node (ref "U1") (pin "112") (pinfunction "PC11_112") (pintype "bidirectional"))
    )
    (net (code "108") (name "/USART3_TX") (class "Default")
      (node (ref "JP1") (pin "5") (pinfunction "5_5") (pintype "passive"))
      (node (ref "U1") (pin "111") (pinfunction "PC10_111") (pintype "bidirectional"))
    )
    (net (code "109") (name "GND") (class "Default")
      (node (ref "C1") (pin "2") (pinfunction "GND_2") (pintype "passive"))
      (node (ref "C10") (pin "1") (pinfunction "1_1") (pintype "passive"))
      (node (ref "C11") (pin "2") (pinfunction "2_2") (pintype "passive"))
      (node (ref "C12") (pin "2") (pinfunction "2_2") (pintype "passive"))
      (node (ref "C13") (pin "2") (pinfunction "2_2") (pintype "passive"))
      (node (ref "C14") (pin "2") (pinfunction "2_2") (pintype "passive"))
      (node (ref "C15") (pin "2") (pinfunction "2_2") (pintype "passive"))
      (node (ref "C16") (pin "2") (pinfunction "2_2") (pintype "passive"))
      (node (ref "C17") (pin "2") (pinfunction "2_2") (pintype "passive"))
      (node (ref "C18") (pin "2") (pinfunction "2_2") (pintype "passive"))
      (node (ref "C19") (pin "2") (pinfunction "2_2") (pintype "passive"))
      (node (ref "C2") (pin "2") (pinfunction "2_2") (pintype "passive"))
      (node (ref "C20") (pin "2") (pinfunction "2_2") (pintype "passive"))
      (node (ref "C21") (pin "2") (pinfunction "2_2") (pintype "passive"))
      (node (ref "C22") (pin "2") (pinfunction "2_2") (pintype "passive"))
      (node (ref "C23") (pin "2") (pinfunction "2_2") (pintype "passive"))
      (node (ref "C24") (pin "2") (pinfunction "2_2") (pintype "passive"))
      (node (ref "C3") (pin "2") (pinfunction "2_2") (pintype "passive"))
      (node (ref "C4") (pin "2") (pinfunction "GND_2") (pintype "passive"))
      (node (ref "C5") (pin "2") (pinfunction "2_2") (pintype "passive"))
      (node (ref "C6") (pin "2") (pinfunction "2_2") (pintype "passive"))
      (node (ref "C7") (pin "2") (pinfunction "2_2") (pintype "passive"))
      (node (ref "C8") (pin "2") (pinfunction "2_2") (pintype "passive"))
      (node (ref "C9") (pin "1") (pinfunction "1_1") (pintype "passive"))
      (node (ref "JP1") (pin "1") (pinfunction "1_1") (pintype "passive"))
      (node (ref "JP1") (pin "6") (pinfunction "6_6") (pintype "passive"))
      (node (ref "JP1") (pin "7") (pinfunction "7_7") (pintype "passive"))
      (node (ref "JP2") (pin "2") (pinfunction "2_2") (pintype "passive"))
      (node (ref "JP3") (pin "1") (pinfunction "1_1") (pintype "passive"))
      (node (ref "JP3") (pin "11") (pinfunction "11_11") (pintype "passive"))
      (node (ref "JP3") (pin "13") (pinfunction "13_13") (pintype "passive"))
      (node (ref "JP3") (pin "15") (pinfunction "15_15") (pintype "passive"))
      (node (ref "JP3") (pin "17") (pinfunction "17_17") (pintype "passive"))
      (node (ref "JP3") (pin "19") (pinfunction "19_19") (pintype "passive"))
      (node (ref "JP3") (pin "21") (pinfunction "21_21") (pintype "passive"))
      (node (ref "JP3") (pin "23") (pinfunction "23_23") (pintype "passive"))
      (node (ref "JP3") (pin "3") (pinfunction "3_3") (pintype "passive"))
      (node (ref "JP3") (pin "5") (pinfunction "5_5") (pintype "passive"))
      (node (ref "JP3") (pin "7") (pinfunction "7_7") (pintype "passive"))
      (node (ref "JP3") (pin "9") (pinfunction "9_9") (pintype "passive"))
      (node (ref "LED1") (pin "2") (pinfunction "K_2") (pintype "passive"))
      (node (ref "Q1") (pin "1") (pinfunction "E_1") (pintype "passive"))
      (node (ref "R6") (pin "2") (pinfunction "2_2") (pintype "passive"))
      (node (ref "SW2") (pin "2") (pinfunction "2_2") (pintype "passive"))
      (node (ref "SW2") (pin "3") (pinfunction "3_3") (pintype "passive"))
      (node (ref "U1") (pin "107") (pinfunction "VSS_2_107") (pintype "power_in"))
      (node (ref "U1") (pin "120") (pinfunction "VSS_10_120") (pintype "power_in"))
      (node (ref "U1") (pin "130") (pinfunction "VSS_11_130") (pintype "power_in"))
      (node (ref "U1") (pin "143") (pinfunction "VSS_3_143") (pintype "power_in"))
      (node (ref "U1") (pin "16") (pinfunction "VSS_5_16") (pintype "power_in"))
      (node (ref "U1") (pin "30") (pinfunction "VSSA_30") (pintype "power_in"))
      (node (ref "U1") (pin "31") (pinfunction "VREF-_31") (pintype "power_in"))
      (node (ref "U1") (pin "38") (pinfunction "VSS_4_38") (pintype "power_in"))
      (node (ref "U1") (pin "51") (pinfunction "VSS_6_51") (pintype "power_in"))
      (node (ref "U1") (pin "61") (pinfunction "VSS_7_61") (pintype "power_in"))
      (node (ref "U1") (pin "71") (pinfunction "VSS_1_71") (pintype "power_in"))
      (node (ref "U1") (pin "83") (pinfunction "VSS_8_83") (pintype "power_in"))
      (node (ref "U1") (pin "94") (pinfunction "VSS_9_94") (pintype "power_in"))
      (node (ref "U2") (pin "1") (pinfunction "ISEN_A_1") (pintype "passive"))
      (node (ref "U2") (pin "15") (pinfunction "ISEN_B_15") (pintype "passive"))
      (node (ref "U2") (pin "8") (pinfunction "GND_8") (pintype "power_in"))
      (node (ref "UART1") (pin "2") (pinfunction "2_2") (pintype "passive"))
      (node (ref "VD5") (pin "1") (pinfunction "A_1") (pintype "passive"))
      (node (ref "VD6") (pin "1") (pinfunction "A_1") (pintype "passive"))
      (node (ref "VD7") (pin "1") (pinfunction "A_1") (pintype "passive"))
      (node (ref "VD8") (pin "1") (pinfunction "A_1") (pintype "passive"))
      (node (ref "VR1") (pin "1") (pinfunction "GND_1") (pintype "passive"))
      (node (ref "VR2") (pin "1") (pinfunction "GND_1") (pintype "passive"))
      (node (ref "boot") (pin "5") (pinfunction "5_5") (pintype "passive"))
      (node (ref "boot") (pin "6") (pinfunction "6_6") (pintype "passive"))
      (node (ref "mpu9250") (pin "2") (pinfunction "2_2") (pintype "passive"))
      (node (ref "swd") (pin "3") (pinfunction "3_3") (pintype "passive"))
    )
    (net (code "110") (name "Net-(LED1-A)") (class "Default")
      (node (ref "LED1") (pin "1") (pinfunction "A_1") (pintype "passive"))
      (node (ref "R1") (pin "2") (pinfunction "2_2") (pintype "passive"))
    )
    (net (code "111") (name "Net-(Q1-C)") (class "Default")
      (node (ref "B1") (pin "2") (pinfunction "2_2") (pintype "passive"))
      (node (ref "Q1") (pin "3") (pinfunction "C_3") (pintype "passive"))
    )
    (net (code "112") (name "Net-(R4-Pad2)") (class "Default")
      (node (ref "R4") (pin "2") (pinfunction "2_2") (pintype "passive"))
      (node (ref "boot") (pin "3") (pinfunction "3_3") (pintype "passive"))
    )
    (net (code "113") (name "Net-(R5-Pad2)") (class "Default")
      (node (ref "R5") (pin "2") (pinfunction "2_2") (pintype "passive"))
      (node (ref "boot") (pin "4") (pinfunction "4_4") (pintype "passive"))
    )
    (net (code "114") (name "Net-(U1A-PC14-OSC32_IN)") (class "Default")
      (node (ref "C9") (pin "2") (pinfunction "2_2") (pintype "passive"))
      (node (ref "U1") (pin "8") (pinfunction "PC14-OSC32_IN_8") (pintype "bidirectional"))
      (node (ref "X2") (pin "1") (pinfunction "1_1") (pintype "passive"))
    )
    (net (code "115") (name "Net-(U1A-PC15-OSC32_OUT)") (class "Default")
      (node (ref "C10") (pin "2") (pinfunction "2_2") (pintype "passive"))
      (node (ref "U1") (pin "9") (pinfunction "PC15-OSC32_OUT_9") (pintype "bidirectional"))
      (node (ref "X2") (pin "2") (pinfunction "2_2") (pintype "passive"))
    )
    (net (code "116") (name "Net-(U1B-OSC_IN)") (class "Default")
      (node (ref "C8") (pin "1") (pinfunction "1_1") (pintype "passive"))
      (node (ref "R2") (pin "2") (pinfunction "2_2") (pintype "passive"))
      (node (ref "U1") (pin "23") (pinfunction "OSC_IN_23") (pintype "input"))
      (node (ref "X1") (pin "2") (pinfunction "2_2") (pintype "passive"))
    )
    (net (code "117") (name "Net-(U1B-OSC_OUT)") (class "Default")
      (node (ref "C7") (pin "1") (pinfunction "1_1") (pintype "passive"))
      (node (ref "R2") (pin "1") (pinfunction "1_1") (pintype "passive"))
      (node (ref "U1") (pin "24") (pinfunction "OSC_OUT_24") (pintype "passive"))
      (node (ref "X1") (pin "1") (pinfunction "1_1") (pintype "passive"))
    )
    (net (code "118") (name "Net-(U2-IN1)") (class "Default")
      (node (ref "JP4") (pin "2") (pinfunction "2_2") (pintype "passive"))
      (node (ref "U2") (pin "5") (pinfunction "IN1_5") (pintype "input"))
    )
    (net (code "119") (name "Net-(U2-IN2)") (class "Default")
      (node (ref "JP4") (pin "4") (pinfunction "4_4") (pintype "passive"))
      (node (ref "U2") (pin "7") (pinfunction "IN2_7") (pintype "input"))
    )
    (net (code "120") (name "Net-(U2-IN3)") (class "Default")
      (node (ref "JP4") (pin "6") (pinfunction "6_6") (pintype "passive"))
      (node (ref "U2") (pin "10") (pinfunction "IN3_10") (pintype "input"))
    )
    (net (code "121") (name "Net-(U2-IN4)") (class "Default")
      (node (ref "JP4") (pin "8") (pinfunction "8_8") (pintype "passive"))
      (node (ref "U2") (pin "12") (pinfunction "IN4_12") (pintype "input"))
    )
    (net (code "122") (name "Net-(U2-OUT1)") (class "Default")
      (node (ref "U2") (pin "2") (pinfunction "OUT1_2") (pintype "output"))
      (node (ref "VD1") (pin "1") (pinfunction "A_1") (pintype "passive"))
      (node (ref "VD5") (pin "2") (pinfunction "K_2") (pintype "passive"))
      (node (ref "motor1") (pin "1") (pinfunction "1_1") (pintype "passive"))
    )
    (net (code "123") (name "Net-(U2-OUT2)") (class "Default")
      (node (ref "U2") (pin "3") (pinfunction "OUT2_3") (pintype "output"))
      (node (ref "VD2") (pin "1") (pinfunction "A_1") (pintype "passive"))
      (node (ref "VD6") (pin "2") (pinfunction "K_2") (pintype "passive"))
      (node (ref "motor1") (pin "2") (pinfunction "2_2") (pintype "passive"))
    )
    (net (code "124") (name "Net-(U2-OUT3)") (class "Default")
      (node (ref "U2") (pin "13") (pinfunction "OUT3_13") (pintype "output"))
      (node (ref "VD3") (pin "1") (pinfunction "A_1") (pintype "passive"))
      (node (ref "VD7") (pin "2") (pinfunction "K_2") (pintype "passive"))
      (node (ref "motor2") (pin "1") (pinfunction "1_1") (pintype "passive"))
    )
    (net (code "125") (name "Net-(U2-OUT4)") (class "Default")
      (node (ref "U2") (pin "14") (pinfunction "OUT4_14") (pintype "output"))
      (node (ref "VD4") (pin "1") (pinfunction "A_1") (pintype "passive"))
      (node (ref "VD8") (pin "2") (pinfunction "K_2") (pintype "passive"))
      (node (ref "motor2") (pin "2") (pinfunction "2_2") (pintype "passive"))
    )
    (net (code "126") (name "VBAT") (class "Default")
      (node (ref "C11") (pin "1") (pinfunction "1_1") (pintype "passive"))
      (node (ref "JP2") (pin "1") (pinfunction "1_1") (pintype "passive"))
      (node (ref "SW1") (pin "2") (pinfunction "COM2_2") (pintype "passive"))
      (node (ref "SW1") (pin "5") (pinfunction "COM2_5") (pintype "passive"))
      (node (ref "U2") (pin "4") (pinfunction "VS_4") (pintype "power_in"))
      (node (ref "VD1") (pin "2") (pinfunction "K_2") (pintype "passive"))
      (node (ref "VD2") (pin "2") (pinfunction "K_2") (pintype "passive"))
      (node (ref "VD3") (pin "2") (pinfunction "K_2") (pintype "passive"))
      (node (ref "VD4") (pin "2") (pinfunction "K_2") (pintype "passive"))
    )
    (net (code "127") (name "VCC3.3") (class "Default")
      (node (ref "C1") (pin "1") (pinfunction "VCC_1") (pintype "passive"))
      (node (ref "C12") (pin "1") (pinfunction "1_1") (pintype "passive"))
      (node (ref "C13") (pin "1") (pinfunction "1_1") (pintype "passive"))
      (node (ref "C14") (pin "1") (pinfunction "1_1") (pintype "passive"))
      (node (ref "C15") (pin "1") (pinfunction "1_1") (pintype "passive"))
      (node (ref "C16") (pin "1") (pinfunction "1_1") (pintype "passive"))
      (node (ref "C17") (pin "1") (pinfunction "1_1") (pintype "passive"))
      (node (ref "C18") (pin "1") (pinfunction "1_1") (pintype "passive"))
      (node (ref "C19") (pin "1") (pinfunction "1_1") (pintype "passive"))
      (node (ref "C20") (pin "1") (pinfunction "1_1") (pintype "passive"))
      (node (ref "C21") (pin "1") (pinfunction "1_1") (pintype "passive"))
      (node (ref "C22") (pin "1") (pinfunction "1_1") (pintype "passive"))
      (node (ref "C23") (pin "1") (pinfunction "1_1") (pintype "passive"))
      (node (ref "C3") (pin "1") (pinfunction "1_1") (pintype "passive"))
      (node (ref "R1") (pin "1") (pinfunction "1_1") (pintype "passive"))
      (node (ref "R3") (pin "2") (pinfunction "2_2") (pintype "passive"))
      (node (ref "R7") (pin "2") (pinfunction "2_2") (pintype "passive"))
      (node (ref "U1") (pin "108") (pinfunction "VDD_2_108") (pintype "power_in"))
      (node (ref "U1") (pin "121") (pinfunction "VDD_10_121") (pintype "power_in"))
      (node (ref "U1") (pin "131") (pinfunction "VDD_11_131") (pintype "power_in"))
      (node (ref "U1") (pin "144") (pinfunction "VDD_3_144") (pintype "power_in"))
      (node (ref "U1") (pin "17") (pinfunction "VDD_5_17") (pintype "power_in"))
      (node (ref "U1") (pin "39") (pinfunction "VDD_4_39") (pintype "power_in"))
      (node (ref "U1") (pin "52") (pinfunction "VDD_6_52") (pintype "power_in"))
      (node (ref "U1") (pin "6") (pinfunction "VBAT_6") (pintype "power_in"))
      (node (ref "U1") (pin "62") (pinfunction "VDD_7_62") (pintype "power_in"))
      (node (ref "U1") (pin "72") (pinfunction "VDD_1_72") (pintype "power_in"))
      (node (ref "U1") (pin "84") (pinfunction "VDD_8_84") (pintype "power_in"))
      (node (ref "U1") (pin "95") (pinfunction "VDD_9_95") (pintype "power_in"))
      (node (ref "VR1") (pin "2") (pinfunction "Vout_2") (pintype "passive"))
      (node (ref "boot") (pin "1") (pinfunction "1_1") (pintype "passive"))
      (node (ref "boot") (pin "2") (pinfunction "2_2") (pintype "passive"))
      (node (ref "swd") (pin "1") (pinfunction "1_1") (pintype "passive"))
    )
    (net (code "128") (name "VCC5") (class "Default")
      (node (ref "B1") (pin "1") (pinfunction "1_1") (pintype "passive"))
      (node (ref "C2") (pin "1") (pinfunction "1_1") (pintype "passive"))
      (node (ref "C5") (pin "1") (pinfunction "1_1") (pintype "passive"))
      (node (ref "JP1") (pin "2") (pinfunction "2_2") (pintype "passive"))
      (node (ref "JP3") (pin "10") (pinfunction "10_10") (pintype "passive"))
      (node (ref "JP3") (pin "12") (pinfunction "12_12") (pintype "passive"))
      (node (ref "JP3") (pin "14") (pinfunction "14_14") (pintype "passive"))
      (node (ref "JP3") (pin "16") (pinfunction "16_16") (pintype "passive"))
      (node (ref "JP3") (pin "18") (pinfunction "18_18") (pintype "passive"))
      (node (ref "JP3") (pin "2") (pinfunction "2_2") (pintype "passive"))
      (node (ref "JP3") (pin "20") (pinfunction "20_20") (pintype "passive"))
      (node (ref "JP3") (pin "22") (pinfunction "22_22") (pintype "passive"))
      (node (ref "JP3") (pin "24") (pinfunction "24_24") (pintype "passive"))
      (node (ref "JP3") (pin "4") (pinfunction "4_4") (pintype "passive"))
      (node (ref "JP3") (pin "6") (pinfunction "6_6") (pintype "passive"))
      (node (ref "JP3") (pin "8") (pinfunction "8_8") (pintype "passive"))
      (node (ref "SW1") (pin "1") (pinfunction "NC1_1") (pintype "passive"))
      (node (ref "SW1") (pin "6") (pinfunction "NC2_6") (pintype "passive"))
      (node (ref "U2") (pin "9") (pinfunction "VSS_9") (pintype "power_in"))
      (node (ref "UART1") (pin "1") (pinfunction "1_1") (pintype "passive"))
      (node (ref "VR1") (pin "3") (pinfunction "Vin_3") (pintype "passive"))
      (node (ref "VR2") (pin "3") (pinfunction "Vin_3") (pintype "passive"))
      (node (ref "mpu9250") (pin "1") (pinfunction "1_1") (pintype "passive"))
    )
    (net (code "129") (name "VREF+") (class "Default")
      (node (ref "C4") (pin "1") (pinfunction "VCC_1") (pintype "passive"))
      (node (ref "C6") (pin "1") (pinfunction "1_1") (pintype "passive"))
      (node (ref "U1") (pin "32") (pinfunction "VREF+_32") (pintype "power_in"))
      (node (ref "U1") (pin "33") (pinfunction "VDDA_33") (pintype "power_in"))
      (node (ref "VR2") (pin "2") (pinfunction "Vout_2") (pintype "passive"))
    )
    (net (code "130") (name "unconnected-(JP1-Pad3)") (class "Default")
      (node (ref "JP1") (pin "3") (pinfunction "3_3") (pintype "passive+no_connect"))
    )
    (net (code "131") (name "unconnected-(SW1-NO1-Pad3)") (class "Default")
      (node (ref "SW1") (pin "3") (pinfunction "NO1_3") (pintype "passive"))
    )
    (net (code "132") (name "unconnected-(SW1-NO2-Pad4)") (class "Default")
      (node (ref "SW1") (pin "4") (pinfunction "NO2_4") (pintype "passive"))
    )
    (net (code "133") (name "unconnected-(U1A-PB4-Pad134)") (class "Default")
      (node (ref "U1") (pin "134") (pinfunction "PB4_134") (pintype "bidirectional"))
    )
    (net (code "134") (name "unconnected-(U1A-PB5-Pad135)") (class "Default")
      (node (ref "U1") (pin "135") (pinfunction "PB5_135") (pintype "bidirectional"))
    )
    (net (code "135") (name "unconnected-(U1A-PC12-Pad113)") (class "Default")
      (node (ref "U1") (pin "113") (pinfunction "PC12_113") (pintype "bidirectional"))
    )
    (net (code "136") (name "unconnected-(U1A-PC13-TAMPER-RTC-Pad7)") (class "Default")
      (node (ref "U1") (pin "7") (pinfunction "PC13-TAMPER-RTC_7") (pintype "bidirectional"))
    )
    (net (code "137") (name "unconnected-(U1B-NC-Pad106)") (class "Default")
      (node (ref "U1") (pin "106") (pinfunction "NC_106") (pintype "passive"))
    )
    (net (code "138") (name "unconnected-(mpu9250-Pad5)") (class "Default")
      (node (ref "mpu9250") (pin "5") (pinfunction "5_5") (pintype "passive+no_connect"))
    )
    (net (code "139") (name "unconnected-(mpu9250-Pad6)") (class "Default")
      (node (ref "mpu9250") (pin "6") (pinfunction "6_6") (pintype "passive+no_connect"))
    )
    (net (code "140") (name "unconnected-(mpu9250-Pad7)") (class "Default")
      (node (ref "mpu9250") (pin "7") (pinfunction "7_7") (pintype "passive+no_connect"))
    )
    (net (code "141") (name "unconnected-(mpu9250-Pad8)") (class "Default")
      (node (ref "mpu9250") (pin "8") (pinfunction "8_8") (pintype "passive+no_connect"))
    )
    (net (code "142") (name "unconnected-(mpu9250-Pad9)") (class "Default")
      (node (ref "mpu9250") (pin "9") (pinfunction "9_9") (pintype "passive+no_connect"))
    )
    (net (code "143") (name "unconnected-(mpu9250-Pad10)") (class "Default")
      (node (ref "mpu9250") (pin "10") (pinfunction "10_10") (pintype "passive+no_connect"))
    )
  )
)
